# LED.net
KiCad netlist of a schematic drawn in Altium Designer
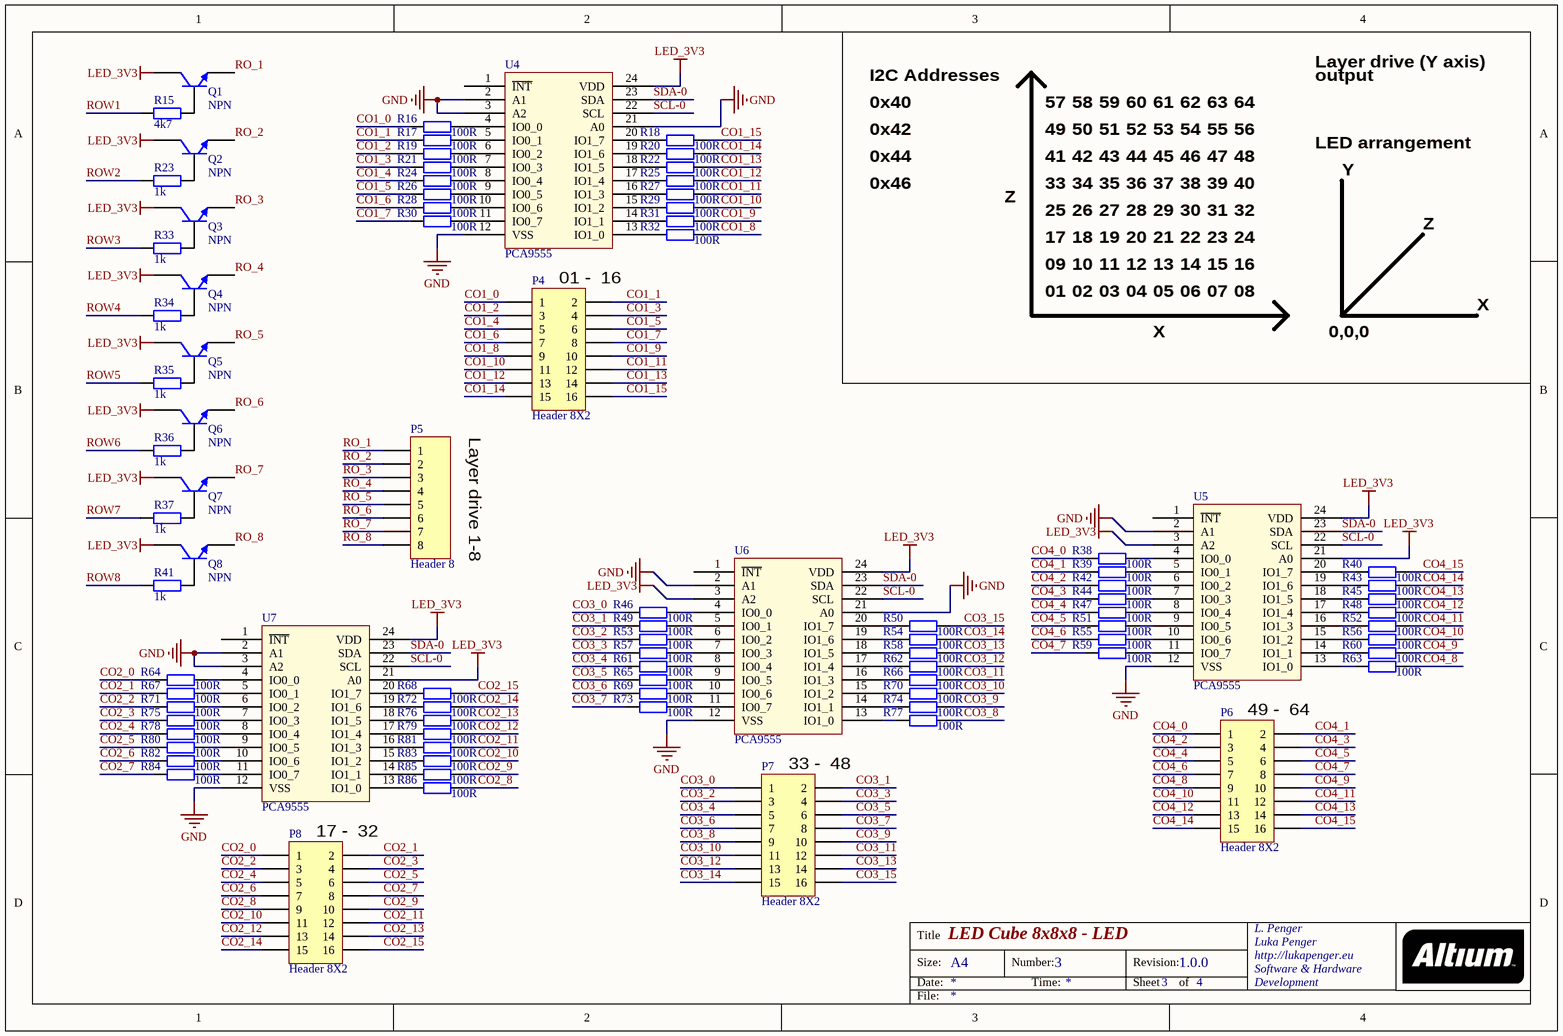
[diagram p0: LED.SchDoc]

(export (version "E")
  (design (tool "Eeschema 10.0.6"))
  (components
    (comp (ref "P4")
      (value "Header 8X2")
      (footprint "HDR2X8")
      (description "Header, 8-Pin, Dual row")
      (fields (field (name "PUBLISHER") "Altium Limited"))
      (libsource (lib "Miscellaneous Connectors") (part "Header 8X2"))
    )
    (comp (ref "P5")
      (value "Header 8")
      (footprint "HDR1X8")
      (description "Header, 8-Pin")
      (fields (field (name "PUBLISHER") "Altium Limited"))
      (libsource (lib "Miscellaneous Connectors") (part "Header 8"))
    )
    (comp (ref "P6")
      (value "Header 8X2")
      (footprint "HDR2X8")
      (description "Header, 8-Pin, Dual row")
      (fields (field (name "PUBLISHER") "Altium Limited"))
      (libsource (lib "Miscellaneous Connectors") (part "Header 8X2"))
    )
    (comp (ref "P7")
      (value "Header 8X2")
      (footprint "HDR2X8")
      (description "Header, 8-Pin, Dual row")
      (fields (field (name "PUBLISHER") "Altium Limited"))
      (libsource (lib "Miscellaneous Connectors") (part "Header 8X2"))
    )
    (comp (ref "P8")
      (value "Header 8X2")
      (footprint "HDR2X8")
      (description "Header, 8-Pin, Dual row")
      (fields (field (name "PUBLISHER") "Altium Limited"))
      (libsource (lib "Miscellaneous Connectors") (part "Header 8X2"))
    )
    (comp (ref "Q1")
      (value "NPN")
      (footprint "SOT23_L")
      (description "NPN Bipolar Transistor")
      (fields (field (name "PUBLISHER") "Altium Limited"))
      (libsource (lib "Miscellaneous Devices") (part "NPN"))
    )
    (comp (ref "Q2")
      (value "NPN")
      (footprint "SOT23_L")
      (description "NPN Bipolar Transistor")
      (fields (field (name "PUBLISHER") "Altium Limited"))
      (libsource (lib "Miscellaneous Devices") (part "NPN"))
    )
    (comp (ref "Q3")
      (value "NPN")
      (footprint "SOT23_L")
      (description "NPN Bipolar Transistor")
      (fields (field (name "PUBLISHER") "Altium Limited"))
      (libsource (lib "Miscellaneous Devices") (part "NPN"))
    )
    (comp (ref "Q4")
      (value "NPN")
      (footprint "SOT23_L")
      (description "NPN Bipolar Transistor")
      (fields (field (name "PUBLISHER") "Altium Limited"))
      (libsource (lib "Miscellaneous Devices") (part "NPN"))
    )
    (comp (ref "Q5")
      (value "NPN")
      (footprint "SOT23_L")
      (description "NPN Bipolar Transistor")
      (fields (field (name "PUBLISHER") "Altium Limited"))
      (libsource (lib "Miscellaneous Devices") (part "NPN"))
    )
    (comp (ref "Q6")
      (value "NPN")
      (footprint "SOT23_L")
      (description "NPN Bipolar Transistor")
      (fields (field (name "PUBLISHER") "Altium Limited"))
      (libsource (lib "Miscellaneous Devices") (part "NPN"))
    )
    (comp (ref "Q7")
      (value "NPN")
      (footprint "SOT23_L")
      (description "NPN Bipolar Transistor")
      (fields (field (name "PUBLISHER") "Altium Limited"))
      (libsource (lib "Miscellaneous Devices") (part "NPN"))
    )
    (comp (ref "Q8")
      (value "NPN")
      (footprint "SOT23_L")
      (description "NPN Bipolar Transistor")
      (fields (field (name "PUBLISHER") "Altium Limited"))
      (libsource (lib "Miscellaneous Devices") (part "NPN"))
    )
    (comp (ref "R15")
      (value "4k7")
      (footprint "6-0805_N")
      (description "Resistor")
      (fields (field (name "PUBLISHER") "Altium Limited"))
      (libsource (lib "") (part "Res2_1"))
    )
    (comp (ref "R16")
      (value "100R")
      (footprint "6-0805_L")
      (description "Resistor")
      (fields (field (name "PUBLISHER") "Altium Limited"))
      (libsource (lib "Miscellaneous Devices") (part "Res2"))
    )
    (comp (ref "R17")
      (value "100R")
      (footprint "6-0805_L")
      (description "Resistor")
      (fields (field (name "PUBLISHER") "Altium Limited"))
      (libsource (lib "Miscellaneous Devices") (part "Res2"))
    )
    (comp (ref "R18")
      (value "100R")
      (footprint "6-0805_L")
      (description "Resistor")
      (fields (field (name "PUBLISHER") "Altium Limited"))
      (libsource (lib "Miscellaneous Devices") (part "Res2"))
    )
    (comp (ref "R19")
      (value "100R")
      (footprint "6-0805_L")
      (description "Resistor")
      (fields (field (name "PUBLISHER") "Altium Limited"))
      (libsource (lib "Miscellaneous Devices") (part "Res2"))
    )
    (comp (ref "R20")
      (value "100R")
      (footprint "6-0805_L")
      (description "Resistor")
      (fields (field (name "PUBLISHER") "Altium Limited"))
      (libsource (lib "Miscellaneous Devices") (part "Res2"))
    )
    (comp (ref "R21")
      (value "100R")
      (footprint "6-0805_L")
      (description "Resistor")
      (fields (field (name "PUBLISHER") "Altium Limited"))
      (libsource (lib "Miscellaneous Devices") (part "Res2"))
    )
    (comp (ref "R22")
      (value "100R")
      (footprint "6-0805_L")
      (description "Resistor")
      (fields (field (name "PUBLISHER") "Altium Limited"))
      (libsource (lib "Miscellaneous Devices") (part "Res2"))
    )
    (comp (ref "R23")
      (value "1k")
      (footprint "6-0805_N")
      (description "Resistor")
      (fields (field (name "PUBLISHER") "Altium Limited"))
      (libsource (lib "") (part "Res2_1"))
    )
    (comp (ref "R24")
      (value "100R")
      (footprint "6-0805_L")
      (description "Resistor")
      (fields (field (name "PUBLISHER") "Altium Limited"))
      (libsource (lib "Miscellaneous Devices") (part "Res2"))
    )
    (comp (ref "R25")
      (value "100R")
      (footprint "6-0805_L")
      (description "Resistor")
      (fields (field (name "PUBLISHER") "Altium Limited"))
      (libsource (lib "Miscellaneous Devices") (part "Res2"))
    )
    (comp (ref "R26")
      (value "100R")
      (footprint "6-0805_L")
      (description "Resistor")
      (fields (field (name "PUBLISHER") "Altium Limited"))
      (libsource (lib "Miscellaneous Devices") (part "Res2"))
    )
    (comp (ref "R27")
      (value "100R")
      (footprint "6-0805_L")
      (description "Resistor")
      (fields (field (name "PUBLISHER") "Altium Limited"))
      (libsource (lib "Miscellaneous Devices") (part "Res2"))
    )
    (comp (ref "R28")
      (value "100R")
      (footprint "6-0805_L")
      (description "Resistor")
      (fields (field (name "PUBLISHER") "Altium Limited"))
      (libsource (lib "Miscellaneous Devices") (part "Res2"))
    )
    (comp (ref "R29")
      (value "100R")
      (footprint "6-0805_L")
      (description "Resistor")
      (fields (field (name "PUBLISHER") "Altium Limited"))
      (libsource (lib "Miscellaneous Devices") (part "Res2"))
    )
    (comp (ref "R30")
      (value "100R")
      (footprint "6-0805_L")
      (description "Resistor")
      (fields (field (name "PUBLISHER") "Altium Limited"))
      (libsource (lib "Miscellaneous Devices") (part "Res2"))
    )
    (comp (ref "R31")
      (value "100R")
      (footprint "6-0805_L")
      (description "Resistor")
      (fields (field (name "PUBLISHER") "Altium Limited"))
      (libsource (lib "Miscellaneous Devices") (part "Res2"))
    )
    (comp (ref "R32")
      (value "100R")
      (footprint "6-0805_L")
      (description "Resistor")
      (fields (field (name "PUBLISHER") "Altium Limited"))
      (libsource (lib "Miscellaneous Devices") (part "Res2"))
    )
    (comp (ref "R33")
      (value "1k")
      (footprint "6-0805_N")
      (description "Resistor")
      (fields (field (name "PUBLISHER") "Altium Limited"))
      (libsource (lib "") (part "Res2_1"))
    )
    (comp (ref "R34")
      (value "1k")
      (footprint "6-0805_N")
      (description "Resistor")
      (fields (field (name "PUBLISHER") "Altium Limited"))
      (libsource (lib "") (part "Res2_1"))
    )
    (comp (ref "R35")
      (value "1k")
      (footprint "6-0805_N")
      (description "Resistor")
      (fields (field (name "PUBLISHER") "Altium Limited"))
      (libsource (lib "") (part "Res2_1"))
    )
    (comp (ref "R36")
      (value "1k")
      (footprint "6-0805_N")
      (description "Resistor")
      (fields (field (name "PUBLISHER") "Altium Limited"))
      (libsource (lib "") (part "Res2_1"))
    )
    (comp (ref "R37")
      (value "1k")
      (footprint "6-0805_N")
      (description "Resistor")
      (fields (field (name "PUBLISHER") "Altium Limited"))
      (libsource (lib "") (part "Res2_1"))
    )
    (comp (ref "R38")
      (value "100R")
      (footprint "6-0805_L")
      (description "Resistor")
      (fields (field (name "PUBLISHER") "Altium Limited"))
      (libsource (lib "Miscellaneous Devices") (part "Res2"))
    )
    (comp (ref "R39")
      (value "100R")
      (footprint "6-0805_L")
      (description "Resistor")
      (fields (field (name "PUBLISHER") "Altium Limited"))
      (libsource (lib "Miscellaneous Devices") (part "Res2"))
    )
    (comp (ref "R40")
      (value "100R")
      (footprint "6-0805_L")
      (description "Resistor")
      (fields (field (name "PUBLISHER") "Altium Limited"))
      (libsource (lib "Miscellaneous Devices") (part "Res2"))
    )
    (comp (ref "R41")
      (value "1k")
      (footprint "6-0805_N")
      (description "Resistor")
      (fields (field (name "PUBLISHER") "Altium Limited"))
      (libsource (lib "") (part "Res2_1"))
    )
    (comp (ref "R42")
      (value "100R")
      (footprint "6-0805_L")
      (description "Resistor")
      (fields (field (name "PUBLISHER") "Altium Limited"))
      (libsource (lib "Miscellaneous Devices") (part "Res2"))
    )
    (comp (ref "R43")
      (value "100R")
      (footprint "6-0805_L")
      (description "Resistor")
      (fields (field (name "PUBLISHER") "Altium Limited"))
      (libsource (lib "Miscellaneous Devices") (part "Res2"))
    )
    (comp (ref "R44")
      (value "100R")
      (footprint "6-0805_L")
      (description "Resistor")
      (fields (field (name "PUBLISHER") "Altium Limited"))
      (libsource (lib "Miscellaneous Devices") (part "Res2"))
    )
    (comp (ref "R45")
      (value "100R")
      (footprint "6-0805_L")
      (description "Resistor")
      (fields (field (name "PUBLISHER") "Altium Limited"))
      (libsource (lib "Miscellaneous Devices") (part "Res2"))
    )
    (comp (ref "R46")
      (value "100R")
      (footprint "6-0805_L")
      (description "Resistor")
      (fields (field (name "PUBLISHER") "Altium Limited"))
      (libsource (lib "Miscellaneous Devices") (part "Res2"))
    )
    (comp (ref "R47")
      (value "100R")
      (footprint "6-0805_L")
      (description "Resistor")
      (fields (field (name "PUBLISHER") "Altium Limited"))
      (libsource (lib "Miscellaneous Devices") (part "Res2"))
    )
    (comp (ref "R48")
      (value "100R")
      (footprint "6-0805_L")
      (description "Resistor")
      (fields (field (name "PUBLISHER") "Altium Limited"))
      (libsource (lib "Miscellaneous Devices") (part "Res2"))
    )
    (comp (ref "R49")
      (value "100R")
      (footprint "6-0805_L")
      (description "Resistor")
      (fields (field (name "PUBLISHER") "Altium Limited"))
      (libsource (lib "Miscellaneous Devices") (part "Res2"))
    )
    (comp (ref "R50")
      (value "100R")
      (footprint "6-0805_L")
      (description "Resistor")
      (fields (field (name "PUBLISHER") "Altium Limited"))
      (libsource (lib "Miscellaneous Devices") (part "Res2"))
    )
    (comp (ref "R51")
      (value "100R")
      (footprint "6-0805_L")
      (description "Resistor")
      (fields (field (name "PUBLISHER") "Altium Limited"))
      (libsource (lib "Miscellaneous Devices") (part "Res2"))
    )
    (comp (ref "R52")
      (value "100R")
      (footprint "6-0805_L")
      (description "Resistor")
      (fields (field (name "PUBLISHER") "Altium Limited"))
      (libsource (lib "Miscellaneous Devices") (part "Res2"))
    )
    (comp (ref "R53")
      (value "100R")
      (footprint "6-0805_L")
      (description "Resistor")
      (fields (field (name "PUBLISHER") "Altium Limited"))
      (libsource (lib "Miscellaneous Devices") (part "Res2"))
    )
    (comp (ref "R54")
      (value "100R")
      (footprint "6-0805_L")
      (description "Resistor")
      (fields (field (name "PUBLISHER") "Altium Limited"))
      (libsource (lib "Miscellaneous Devices") (part "Res2"))
    )
    (comp (ref "R55")
      (value "100R")
      (footprint "6-0805_L")
      (description "Resistor")
      (fields (field (name "PUBLISHER") "Altium Limited"))
      (libsource (lib "Miscellaneous Devices") (part "Res2"))
    )
    (comp (ref "R56")
      (value "100R")
      (footprint "6-0805_L")
      (description "Resistor")
      (fields (field (name "PUBLISHER") "Altium Limited"))
      (libsource (lib "Miscellaneous Devices") (part "Res2"))
    )
    (comp (ref "R57")
      (value "100R")
      (footprint "6-0805_L")
      (description "Resistor")
      (fields (field (name "PUBLISHER") "Altium Limited"))
      (libsource (lib "Miscellaneous Devices") (part "Res2"))
    )
    (comp (ref "R58")
      (value "100R")
      (footprint "6-0805_L")
      (description "Resistor")
      (fields (field (name "PUBLISHER") "Altium Limited"))
      (libsource (lib "Miscellaneous Devices") (part "Res2"))
    )
    (comp (ref "R59")
      (value "100R")
      (footprint "6-0805_L")
      (description "Resistor")
      (fields (field (name "PUBLISHER") "Altium Limited"))
      (libsource (lib "Miscellaneous Devices") (part "Res2"))
    )
    (comp (ref "R60")
      (value "100R")
      (footprint "6-0805_L")
      (description "Resistor")
      (fields (field (name "PUBLISHER") "Altium Limited"))
      (libsource (lib "Miscellaneous Devices") (part "Res2"))
    )
    (comp (ref "R61")
      (value "100R")
      (footprint "6-0805_L")
      (description "Resistor")
      (fields (field (name "PUBLISHER") "Altium Limited"))
      (libsource (lib "Miscellaneous Devices") (part "Res2"))
    )
    (comp (ref "R62")
      (value "100R")
      (footprint "6-0805_L")
      (description "Resistor")
      (fields (field (name "PUBLISHER") "Altium Limited"))
      (libsource (lib "Miscellaneous Devices") (part "Res2"))
    )
    (comp (ref "R63")
      (value "100R")
      (footprint "6-0805_L")
      (description "Resistor")
      (fields (field (name "PUBLISHER") "Altium Limited"))
      (libsource (lib "Miscellaneous Devices") (part "Res2"))
    )
    (comp (ref "R64")
      (value "100R")
      (footprint "6-0805_L")
      (description "Resistor")
      (fields (field (name "PUBLISHER") "Altium Limited"))
      (libsource (lib "Miscellaneous Devices") (part "Res2"))
    )
    (comp (ref "R65")
      (value "100R")
      (footprint "6-0805_L")
      (description "Resistor")
      (fields (field (name "PUBLISHER") "Altium Limited"))
      (libsource (lib "Miscellaneous Devices") (part "Res2"))
    )
    (comp (ref "R66")
      (value "100R")
      (footprint "6-0805_L")
      (description "Resistor")
      (fields (field (name "PUBLISHER") "Altium Limited"))
      (libsource (lib "Miscellaneous Devices") (part "Res2"))
    )
    (comp (ref "R67")
      (value "100R")
      (footprint "6-0805_L")
      (description "Resistor")
      (fields (field (name "PUBLISHER") "Altium Limited"))
      (libsource (lib "Miscellaneous Devices") (part "Res2"))
    )
    (comp (ref "R68")
      (value "100R")
      (footprint "6-0805_L")
      (description "Resistor")
      (fields (field (name "PUBLISHER") "Altium Limited"))
      (libsource (lib "Miscellaneous Devices") (part "Res2"))
    )
    (comp (ref "R69")
      (value "100R")
      (footprint "6-0805_L")
      (description "Resistor")
      (fields (field (name "PUBLISHER") "Altium Limited"))
      (libsource (lib "Miscellaneous Devices") (part "Res2"))
    )
    (comp (ref "R70")
      (value "100R")
      (footprint "6-0805_L")
      (description "Resistor")
      (fields (field (name "PUBLISHER") "Altium Limited"))
      (libsource (lib "Miscellaneous Devices") (part "Res2"))
    )
    (comp (ref "R71")
      (value "100R")
      (footprint "6-0805_L")
      (description "Resistor")
      (fields (field (name "PUBLISHER") "Altium Limited"))
      (libsource (lib "Miscellaneous Devices") (part "Res2"))
    )
    (comp (ref "R72")
      (value "100R")
      (footprint "6-0805_L")
      (description "Resistor")
      (fields (field (name "PUBLISHER") "Altium Limited"))
      (libsource (lib "Miscellaneous Devices") (part "Res2"))
    )
    (comp (ref "R73")
      (value "100R")
      (footprint "6-0805_L")
      (description "Resistor")
      (fields (field (name "PUBLISHER") "Altium Limited"))
      (libsource (lib "Miscellaneous Devices") (part "Res2"))
    )
    (comp (ref "R74")
      (value "100R")
      (footprint "6-0805_L")
      (description "Resistor")
      (fields (field (name "PUBLISHER") "Altium Limited"))
      (libsource (lib "Miscellaneous Devices") (part "Res2"))
    )
    (comp (ref "R75")
      (value "100R")
      (footprint "6-0805_L")
      (description "Resistor")
      (fields (field (name "PUBLISHER") "Altium Limited"))
      (libsource (lib "Miscellaneous Devices") (part "Res2"))
    )
    (comp (ref "R76")
      (value "100R")
      (footprint "6-0805_L")
      (description "Resistor")
      (fields (field (name "PUBLISHER") "Altium Limited"))
      (libsource (lib "Miscellaneous Devices") (part "Res2"))
    )
    (comp (ref "R77")
      (value "100R")
      (footprint "6-0805_L")
      (description "Resistor")
      (fields (field (name "PUBLISHER") "Altium Limited"))
      (libsource (lib "Miscellaneous Devices") (part "Res2"))
    )
    (comp (ref "R78")
      (value "100R")
      (footprint "6-0805_L")
      (description "Resistor")
      (fields (field (name "PUBLISHER") "Altium Limited"))
      (libsource (lib "Miscellaneous Devices") (part "Res2"))
    )
    (comp (ref "R79")
      (value "100R")
      (footprint "6-0805_L")
      (description "Resistor")
      (fields (field (name "PUBLISHER") "Altium Limited"))
      (libsource (lib "Miscellaneous Devices") (part "Res2"))
    )
    (comp (ref "R80")
      (value "100R")
      (footprint "6-0805_L")
      (description "Resistor")
      (fields (field (name "PUBLISHER") "Altium Limited"))
      (libsource (lib "Miscellaneous Devices") (part "Res2"))
    )
    (comp (ref "R81")
      (value "100R")
      (footprint "6-0805_L")
      (description "Resistor")
      (fields (field (name "PUBLISHER") "Altium Limited"))
      (libsource (lib "Miscellaneous Devices") (part "Res2"))
    )
    (comp (ref "R82")
      (value "100R")
      (footprint "6-0805_L")
      (description "Resistor")
      (fields (field (name "PUBLISHER") "Altium Limited"))
      (libsource (lib "Miscellaneous Devices") (part "Res2"))
    )
    (comp (ref "R83")
      (value "100R")
      (footprint "6-0805_L")
      (description "Resistor")
      (fields (field (name "PUBLISHER") "Altium Limited"))
      (libsource (lib "Miscellaneous Devices") (part "Res2"))
    )
    (comp (ref "R84")
      (value "100R")
      (footprint "6-0805_L")
      (description "Resistor")
      (fields (field (name "PUBLISHER") "Altium Limited"))
      (libsource (lib "Miscellaneous Devices") (part "Res2"))
    )
    (comp (ref "R85")
      (value "100R")
      (footprint "6-0805_L")
      (description "Resistor")
      (fields (field (name "PUBLISHER") "Altium Limited"))
      (libsource (lib "Miscellaneous Devices") (part "Res2"))
    )
    (comp (ref "R86")
      (value "100R")
      (footprint "6-0805_L")
      (description "Resistor")
      (fields (field (name "PUBLISHER") "Altium Limited"))
      (libsource (lib "Miscellaneous Devices") (part "Res2"))
    )
    (comp (ref "U4")
      (value "PCA9555")
      (footprint "SSOP24_N")
      (description "I2C I/O Ports")
      (libsource (lib "LP_Lib") (part "PCA9555"))
    )
    (comp (ref "U5")
      (value "PCA9555")
      (footprint "SSOP24_N")
      (description "I2C I/O Ports")
      (libsource (lib "LP_Lib") (part "PCA9555"))
    )
    (comp (ref "U6")
      (value "PCA9555")
      (footprint "SSOP24_N")
      (description "I2C I/O Ports")
      (libsource (lib "LP_Lib") (part "PCA9555"))
    )
    (comp (ref "U7")
      (value "PCA9555")
      (footprint "SSOP24_N")
      (description "I2C I/O Ports")
      (libsource (lib "LP_Lib") (part "PCA9555"))
    )
  )
  (nets
    (net (code "1") (name "/CO1_0") (class "Default")
      (node (ref "P4") (pin "1") (pinfunction "1_1") (pintype "passive"))
      (node (ref "R16") (pin "1") (pinfunction "1_1") (pintype "passive"))
    )
    (net (code "2") (name "/CO1_1") (class "Default")
      (node (ref "P4") (pin "2") (pinfunction "2_2") (pintype "passive"))
      (node (ref "R17") (pin "1") (pinfunction "1_1") (pintype "passive"))
    )
    (net (code "3") (name "/CO1_2") (class "Default")
      (node (ref "P4") (pin "3") (pinfunction "3_3") (pintype "passive"))
      (node (ref "R19") (pin "1") (pinfunction "1_1") (pintype "passive"))
    )
    (net (code "4") (name "/CO1_3") (class "Default")
      (node (ref "P4") (pin "4") (pinfunction "4_4") (pintype "passive"))
      (node (ref "R21") (pin "1") (pinfunction "1_1") (pintype "passive"))
    )
    (net (code "5") (name "/CO1_4") (class "Default")
      (node (ref "P4") (pin "5") (pinfunction "5_5") (pintype "passive"))
      (node (ref "R24") (pin "1") (pinfunction "1_1") (pintype "passive"))
    )
    (net (code "6") (name "/CO1_5") (class "Default")
      (node (ref "P4") (pin "6") (pinfunction "6_6") (pintype "passive"))
      (node (ref "R26") (pin "1") (pinfunction "1_1") (pintype "passive"))
    )
    (net (code "7") (name "/CO1_6") (class "Default")
      (node (ref "P4") (pin "7") (pinfunction "7_7") (pintype "passive"))
      (node (ref "R28") (pin "1") (pinfunction "1_1") (pintype "passive"))
    )
    (net (code "8") (name "/CO1_7") (class "Default")
      (node (ref "P4") (pin "8") (pinfunction "8_8") (pintype "passive"))
      (node (ref "R30") (pin "1") (pinfunction "1_1") (pintype "passive"))
    )
    (net (code "9") (name "/CO1_8") (class "Default")
      (node (ref "P4") (pin "9") (pinfunction "9_9") (pintype "passive"))
      (node (ref "R32") (pin "2") (pinfunction "2_2") (pintype "passive"))
    )
    (net (code "10") (name "/CO1_9") (class "Default")
      (node (ref "P4") (pin "10") (pinfunction "10_10") (pintype "passive"))
      (node (ref "R31") (pin "2") (pinfunction "2_2") (pintype "passive"))
    )
    (net (code "11") (name "/CO1_10") (class "Default")
      (node (ref "P4") (pin "11") (pinfunction "11_11") (pintype "passive"))
      (node (ref "R29") (pin "2") (pinfunction "2_2") (pintype "passive"))
    )
    (net (code "12") (name "/CO1_11") (class "Default")
      (node (ref "P4") (pin "12") (pinfunction "12_12") (pintype "passive"))
      (node (ref "R27") (pin "2") (pinfunction "2_2") (pintype "passive"))
    )
    (net (code "13") (name "/CO1_12") (class "Default")
      (node (ref "P4") (pin "13") (pinfunction "13_13") (pintype "passive"))
      (node (ref "R25") (pin "2") (pinfunction "2_2") (pintype "passive"))
    )
    (net (code "14") (name "/CO1_13") (class "Default")
      (node (ref "P4") (pin "14") (pinfunction "14_14") (pintype "passive"))
      (node (ref "R22") (pin "2") (pinfunction "2_2") (pintype "passive"))
    )
    (net (code "15") (name "/CO1_14") (class "Default")
      (node (ref "P4") (pin "15") (pinfunction "15_15") (pintype "passive"))
      (node (ref "R20") (pin "2") (pinfunction "2_2") (pintype "passive"))
    )
    (net (code "16") (name "/CO1_15") (class "Default")
      (node (ref "P4") (pin "16") (pinfunction "16_16") (pintype "passive"))
      (node (ref "R18") (pin "2") (pinfunction "2_2") (pintype "passive"))
    )
    (net (code "17") (name "/CO2_0") (class "Default")
      (node (ref "P8") (pin "1") (pinfunction "1_1") (pintype "passive"))
      (node (ref "R64") (pin "1") (pinfunction "1_1") (pintype "passive"))
    )
    (net (code "18") (name "/CO2_1") (class "Default")
      (node (ref "P8") (pin "2") (pinfunction "2_2") (pintype "passive"))
      (node (ref "R67") (pin "1") (pinfunction "1_1") (pintype "passive"))
    )
    (net (code "19") (name "/CO2_2") (class "Default")
      (node (ref "P8") (pin "3") (pinfunction "3_3") (pintype "passive"))
      (node (ref "R71") (pin "1") (pinfunction "1_1") (pintype "passive"))
    )
    (net (code "20") (name "/CO2_3") (class "Default")
      (node (ref "P8") (pin "4") (pinfunction "4_4") (pintype "passive"))
      (node (ref "R75") (pin "1") (pinfunction "1_1") (pintype "passive"))
    )
    (net (code "21") (name "/CO2_4") (class "Default")
      (node (ref "P8") (pin "5") (pinfunction "5_5") (pintype "passive"))
      (node (ref "R78") (pin "1") (pinfunction "1_1") (pintype "passive"))
    )
    (net (code "22") (name "/CO2_5") (class "Default")
      (node (ref "P8") (pin "6") (pinfunction "6_6") (pintype "passive"))
      (node (ref "R80") (pin "1") (pinfunction "1_1") (pintype "passive"))
    )
    (net (code "23") (name "/CO2_6") (class "Default")
      (node (ref "P8") (pin "7") (pinfunction "7_7") (pintype "passive"))
      (node (ref "R82") (pin "1") (pinfunction "1_1") (pintype "passive"))
    )
    (net (code "24") (name "/CO2_7") (class "Default")
      (node (ref "P8") (pin "8") (pinfunction "8_8") (pintype "passive"))
      (node (ref "R84") (pin "1") (pinfunction "1_1") (pintype "passive"))
    )
    (net (code "25") (name "/CO2_8") (class "Default")
      (node (ref "P8") (pin "9") (pinfunction "9_9") (pintype "passive"))
      (node (ref "R86") (pin "2") (pinfunction "2_2") (pintype "passive"))
    )
    (net (code "26") (name "/CO2_9") (class "Default")
      (node (ref "P8") (pin "10") (pinfunction "10_10") (pintype "passive"))
      (node (ref "R85") (pin "2") (pinfunction "2_2") (pintype "passive"))
    )
    (net (code "27") (name "/CO2_10") (class "Default")
      (node (ref "P8") (pin "11") (pinfunction "11_11") (pintype "passive"))
      (node (ref "R83") (pin "2") (pinfunction "2_2") (pintype "passive"))
    )
    (net (code "28") (name "/CO2_11") (class "Default")
      (node (ref "P8") (pin "12") (pinfunction "12_12") (pintype "passive"))
      (node (ref "R81") (pin "2") (pinfunction "2_2") (pintype "passive"))
    )
    (net (code "29") (name "/CO2_12") (class "Default")
      (node (ref "P8") (pin "13") (pinfunction "13_13") (pintype "passive"))
      (node (ref "R79") (pin "2") (pinfunction "2_2") (pintype "passive"))
    )
    (net (code "30") (name "/CO2_13") (class "Default")
      (node (ref "P8") (pin "14") (pinfunction "14_14") (pintype "passive"))
      (node (ref "R76") (pin "2") (pinfunction "2_2") (pintype "passive"))
    )
    (net (code "31") (name "/CO2_14") (class "Default")
      (node (ref "P8") (pin "15") (pinfunction "15_15") (pintype "passive"))
      (node (ref "R72") (pin "2") (pinfunction "2_2") (pintype "passive"))
    )
    (net (code "32") (name "/CO2_15") (class "Default")
      (node (ref "P8") (pin "16") (pinfunction "16_16") (pintype "passive"))
      (node (ref "R68") (pin "2") (pinfunction "2_2") (pintype "passive"))
    )
    (net (code "33") (name "/CO3_0") (class "Default")
      (node (ref "P7") (pin "1") (pinfunction "1_1") (pintype "passive"))
      (node (ref "R46") (pin "1") (pinfunction "1_1") (pintype "passive"))
    )
    (net (code "34") (name "/CO3_1") (class "Default")
      (node (ref "P7") (pin "2") (pinfunction "2_2") (pintype "passive"))
      (node (ref "R49") (pin "1") (pinfunction "1_1") (pintype "passive"))
    )
    (net (code "35") (name "/CO3_2") (class "Default")
      (node (ref "P7") (pin "3") (pinfunction "3_3") (pintype "passive"))
      (node (ref "R53") (pin "1") (pinfunction "1_1") (pintype "passive"))
    )
    (net (code "36") (name "/CO3_3") (class "Default")
      (node (ref "P7") (pin "4") (pinfunction "4_4") (pintype "passive"))
      (node (ref "R57") (pin "1") (pinfunction "1_1") (pintype "passive"))
    )
    (net (code "37") (name "/CO3_4") (class "Default")
      (node (ref "P7") (pin "5") (pinfunction "5_5") (pintype "passive"))
      (node (ref "R61") (pin "1") (pinfunction "1_1") (pintype "passive"))
    )
    (net (code "38") (name "/CO3_5") (class "Default")
      (node (ref "P7") (pin "6") (pinfunction "6_6") (pintype "passive"))
      (node (ref "R65") (pin "1") (pinfunction "1_1") (pintype "passive"))
    )
    (net (code "39") (name "/CO3_6") (class "Default")
      (node (ref "P7") (pin "7") (pinfunction "7_7") (pintype "passive"))
      (node (ref "R69") (pin "1") (pinfunction "1_1") (pintype "passive"))
    )
    (net (code "40") (name "/CO3_7") (class "Default")
      (node (ref "P7") (pin "8") (pinfunction "8_8") (pintype "passive"))
      (node (ref "R73") (pin "1") (pinfunction "1_1") (pintype "passive"))
    )
    (net (code "41") (name "/CO3_8") (class "Default")
      (node (ref "P7") (pin "9") (pinfunction "9_9") (pintype "passive"))
      (node (ref "R77") (pin "2") (pinfunction "2_2") (pintype "passive"))
    )
    (net (code "42") (name "/CO3_9") (class "Default")
      (node (ref "P7") (pin "10") (pinfunction "10_10") (pintype "passive"))
      (node (ref "R74") (pin "2") (pinfunction "2_2") (pintype "passive"))
    )
    (net (code "43") (name "/CO3_10") (class "Default")
      (node (ref "P7") (pin "11") (pinfunction "11_11") (pintype "passive"))
      (node (ref "R70") (pin "2") (pinfunction "2_2") (pintype "passive"))
    )
    (net (code "44") (name "/CO3_11") (class "Default")
      (node (ref "P7") (pin "12") (pinfunction "12_12") (pintype "passive"))
      (node (ref "R66") (pin "2") (pinfunction "2_2") (pintype "passive"))
    )
    (net (code "45") (name "/CO3_12") (class "Default")
      (node (ref "P7") (pin "13") (pinfunction "13_13") (pintype "passive"))
      (node (ref "R62") (pin "2") (pinfunction "2_2") (pintype "passive"))
    )
    (net (code "46") (name "/CO3_13") (class "Default")
      (node (ref "P7") (pin "14") (pinfunction "14_14") (pintype "passive"))
      (node (ref "R58") (pin "2") (pinfunction "2_2") (pintype "passive"))
    )
    (net (code "47") (name "/CO3_14") (class "Default")
      (node (ref "P7") (pin "15") (pinfunction "15_15") (pintype "passive"))
      (node (ref "R54") (pin "2") (pinfunction "2_2") (pintype "passive"))
    )
    (net (code "48") (name "/CO3_15") (class "Default")
      (node (ref "P7") (pin "16") (pinfunction "16_16") (pintype "passive"))
      (node (ref "R50") (pin "2") (pinfunction "2_2") (pintype "passive"))
    )
    (net (code "49") (name "/CO4_0") (class "Default")
      (node (ref "P6") (pin "1") (pinfunction "1_1") (pintype "passive"))
      (node (ref "R38") (pin "1") (pinfunction "1_1") (pintype "passive"))
    )
    (net (code "50") (name "/CO4_1") (class "Default")
      (node (ref "P6") (pin "2") (pinfunction "2_2") (pintype "passive"))
      (node (ref "R39") (pin "1") (pinfunction "1_1") (pintype "passive"))
    )
    (net (code "51") (name "/CO4_2") (class "Default")
      (node (ref "P6") (pin "3") (pinfunction "3_3") (pintype "passive"))
      (node (ref "R42") (pin "1") (pinfunction "1_1") (pintype "passive"))
    )
    (net (code "52") (name "/CO4_3") (class "Default")
      (node (ref "P6") (pin "4") (pinfunction "4_4") (pintype "passive"))
      (node (ref "R44") (pin "1") (pinfunction "1_1") (pintype "passive"))
    )
    (net (code "53") (name "/CO4_4") (class "Default")
      (node (ref "P6") (pin "5") (pinfunction "5_5") (pintype "passive"))
      (node (ref "R47") (pin "1") (pinfunction "1_1") (pintype "passive"))
    )
    (net (code "54") (name "/CO4_5") (class "Default")
      (node (ref "P6") (pin "6") (pinfunction "6_6") (pintype "passive"))
      (node (ref "R51") (pin "1") (pinfunction "1_1") (pintype "passive"))
    )
    (net (code "55") (name "/CO4_6") (class "Default")
      (node (ref "P6") (pin "7") (pinfunction "7_7") (pintype "passive"))
      (node (ref "R55") (pin "1") (pinfunction "1_1") (pintype "passive"))
    )
    (net (code "56") (name "/CO4_7") (class "Default")
      (node (ref "P6") (pin "8") (pinfunction "8_8") (pintype "passive"))
      (node (ref "R59") (pin "1") (pinfunction "1_1") (pintype "passive"))
    )
    (net (code "57") (name "/CO4_8") (class "Default")
      (node (ref "P6") (pin "9") (pinfunction "9_9") (pintype "passive"))
      (node (ref "R63") (pin "2") (pinfunction "2_2") (pintype "passive"))
    )
    (net (code "58") (name "/CO4_9") (class "Default")
      (node (ref "P6") (pin "10") (pinfunction "10_10") (pintype "passive"))
      (node (ref "R60") (pin "2") (pinfunction "2_2") (pintype "passive"))
    )
    (net (code "59") (name "/CO4_10") (class "Default")
      (node (ref "P6") (pin "11") (pinfunction "11_11") (pintype "passive"))
      (node (ref "R56") (pin "2") (pinfunction "2_2") (pintype "passive"))
    )
    (net (code "60") (name "/CO4_11") (class "Default")
      (node (ref "P6") (pin "12") (pinfunction "12_12") (pintype "passive"))
      (node (ref "R52") (pin "2") (pinfunction "2_2") (pintype "passive"))
    )
    (net (code "61") (name "/CO4_12") (class "Default")
      (node (ref "P6") (pin "13") (pinfunction "13_13") (pintype "passive"))
      (node (ref "R48") (pin "2") (pinfunction "2_2") (pintype "passive"))
    )
    (net (code "62") (name "/CO4_13") (class "Default")
      (node (ref "P6") (pin "14") (pinfunction "14_14") (pintype "passive"))
      (node (ref "R45") (pin "2") (pinfunction "2_2") (pintype "passive"))
    )
    (net (code "63") (name "/CO4_14") (class "Default")
      (node (ref "P6") (pin "15") (pinfunction "15_15") (pintype "passive"))
      (node (ref "R43") (pin "2") (pinfunction "2_2") (pintype "passive"))
    )
    (net (code "64") (name "/CO4_15") (class "Default")
      (node (ref "P6") (pin "16") (pinfunction "16_16") (pintype "passive"))
      (node (ref "R40") (pin "2") (pinfunction "2_2") (pintype "passive"))
    )
    (net (code "65") (name "/ROW1") (class "Default")
      (node (ref "R15") (pin "2") (pinfunction "2_2") (pintype "passive"))
    )
    (net (code "66") (name "/ROW2") (class "Default")
      (node (ref "R23") (pin "2") (pinfunction "2_2") (pintype "passive"))
    )
    (net (code "67") (name "/ROW3") (class "Default")
      (node (ref "R33") (pin "2") (pinfunction "2_2") (pintype "passive"))
    )
    (net (code "68") (name "/ROW4") (class "Default")
      (node (ref "R34") (pin "2") (pinfunction "2_2") (pintype "passive"))
    )
    (net (code "69") (name "/ROW5") (class "Default")
      (node (ref "R35") (pin "2") (pinfunction "2_2") (pintype "passive"))
    )
    (net (code "70") (name "/ROW6") (class "Default")
      (node (ref "R36") (pin "2") (pinfunction "2_2") (pintype "passive"))
    )
    (net (code "71") (name "/ROW7") (class "Default")
      (node (ref "R37") (pin "2") (pinfunction "2_2") (pintype "passive"))
    )
    (net (code "72") (name "/ROW8") (class "Default")
      (node (ref "R41") (pin "2") (pinfunction "2_2") (pintype "passive"))
    )
    (net (code "73") (name "/RO_1") (class "Default")
      (node (ref "P5") (pin "1") (pinfunction "1_1") (pintype "passive"))
      (node (ref "Q1") (pin "3") (pinfunction "E_3") (pintype "passive"))
    )
    (net (code "74") (name "/RO_2") (class "Default")
      (node (ref "P5") (pin "2") (pinfunction "2_2") (pintype "passive"))
      (node (ref "Q2") (pin "3") (pinfunction "E_3") (pintype "passive"))
    )
    (net (code "75") (name "/RO_3") (class "Default")
      (node (ref "P5") (pin "3") (pinfunction "3_3") (pintype "passive"))
      (node (ref "Q3") (pin "3") (pinfunction "E_3") (pintype "passive"))
    )
    (net (code "76") (name "/RO_4") (class "Default")
      (node (ref "P5") (pin "4") (pinfunction "4_4") (pintype "passive"))
      (node (ref "Q4") (pin "3") (pinfunction "E_3") (pintype "passive"))
    )
    (net (code "77") (name "/RO_5") (class "Default")
      (node (ref "P5") (pin "5") (pinfunction "5_5") (pintype "passive"))
      (node (ref "Q5") (pin "3") (pinfunction "E_3") (pintype "passive"))
    )
    (net (code "78") (name "/RO_6") (class "Default")
      (node (ref "P5") (pin "6") (pinfunction "6_6") (pintype "passive"))
      (node (ref "Q6") (pin "3") (pinfunction "E_3") (pintype "passive"))
    )
    (net (code "79") (name "/RO_7") (class "Default")
      (node (ref "P5") (pin "7") (pinfunction "7_7") (pintype "passive"))
      (node (ref "Q7") (pin "3") (pinfunction "E_3") (pintype "passive"))
    )
    (net (code "80") (name "/RO_8") (class "Default")
      (node (ref "P5") (pin "8") (pinfunction "8_8") (pintype "passive"))
      (node (ref "Q8") (pin "3") (pinfunction "E_3") (pintype "passive"))
    )
    (net (code "81") (name "/SCL-0") (class "Default")
      (node (ref "U4") (pin "22") (pinfunction "SCL_22") (pintype "passive"))
      (node (ref "U5") (pin "22") (pinfunction "SCL_22") (pintype "passive"))
      (node (ref "U6") (pin "22") (pinfunction "SCL_22") (pintype "passive"))
      (node (ref "U7") (pin "22") (pinfunction "SCL_22") (pintype "passive"))
    )
    (net (code "82") (name "/SDA-0") (class "Default")
      (node (ref "U4") (pin "23") (pinfunction "SDA_23") (pintype "passive"))
      (node (ref "U5") (pin "23") (pinfunction "SDA_23") (pintype "passive"))
      (node (ref "U6") (pin "23") (pinfunction "SDA_23") (pintype "passive"))
      (node (ref "U7") (pin "23") (pinfunction "SDA_23") (pintype "passive"))
    )
    (net (code "83") (name "GND") (class "Default")
      (node (ref "U4") (pin "12") (pinfunction "VSS_12") (pintype "passive"))
      (node (ref "U4") (pin "2") (pinfunction "A1_2") (pintype "passive"))
      (node (ref "U4") (pin "21") (pinfunction "A0_21") (pintype "passive"))
      (node (ref "U4") (pin "3") (pinfunction "A2_3") (pintype "passive"))
      (node (ref "U5") (pin "12") (pinfunction "VSS_12") (pintype "passive"))
      (node (ref "U5") (pin "2") (pinfunction "A1_2") (pintype "passive"))
      (node (ref "U6") (pin "12") (pinfunction "VSS_12") (pintype "passive"))
      (node (ref "U6") (pin "2") (pinfunction "A1_2") (pintype "passive"))
      (node (ref "U6") (pin "21") (pinfunction "A0_21") (pintype "passive"))
      (node (ref "U7") (pin "12") (pinfunction "VSS_12") (pintype "passive"))
      (node (ref "U7") (pin "2") (pinfunction "A1_2") (pintype "passive"))
      (node (ref "U7") (pin "3") (pinfunction "A2_3") (pintype "passive"))
    )
    (net (code "84") (name "LED_3V3") (class "Default")
      (node (ref "Q1") (pin "1") (pinfunction "C_1") (pintype "passive"))
      (node (ref "Q2") (pin "1") (pinfunction "C_1") (pintype "passive"))
      (node (ref "Q3") (pin "1") (pinfunction "C_1") (pintype "passive"))
      (node (ref "Q4") (pin "1") (pinfunction "C_1") (pintype "passive"))
      (node (ref "Q5") (pin "1") (pinfunction "C_1") (pintype "passive"))
      (node (ref "Q6") (pin "1") (pinfunction "C_1") (pintype "passive"))
      (node (ref "Q7") (pin "1") (pinfunction "C_1") (pintype "passive"))
      (node (ref "Q8") (pin "1") (pinfunction "C_1") (pintype "passive"))
      (node (ref "U4") (pin "24") (pinfunction "VDD_24") (pintype "passive"))
      (node (ref "U5") (pin "21") (pinfunction "A0_21") (pintype "passive"))
      (node (ref "U5") (pin "24") (pinfunction "VDD_24") (pintype "passive"))
      (node (ref "U5") (pin "3") (pinfunction "A2_3") (pintype "passive"))
      (node (ref "U6") (pin "24") (pinfunction "VDD_24") (pintype "passive"))
      (node (ref "U6") (pin "3") (pinfunction "A2_3") (pintype "passive"))
      (node (ref "U7") (pin "21") (pinfunction "A0_21") (pintype "passive"))
      (node (ref "U7") (pin "24") (pinfunction "VDD_24") (pintype "passive"))
    )
    (net (code "85") (name "Net-(Q1-B)") (class "Default")
      (node (ref "Q1") (pin "2") (pinfunction "B_2") (pintype "passive"))
      (node (ref "R15") (pin "1") (pinfunction "1_1") (pintype "passive"))
    )
    (net (code "86") (name "Net-(Q2-B)") (class "Default")
      (node (ref "Q2") (pin "2") (pinfunction "B_2") (pintype "passive"))
      (node (ref "R23") (pin "1") (pinfunction "1_1") (pintype "passive"))
    )
    (net (code "87") (name "Net-(Q3-B)") (class "Default")
      (node (ref "Q3") (pin "2") (pinfunction "B_2") (pintype "passive"))
      (node (ref "R33") (pin "1") (pinfunction "1_1") (pintype "passive"))
    )
    (net (code "88") (name "Net-(Q4-B)") (class "Default")
      (node (ref "Q4") (pin "2") (pinfunction "B_2") (pintype "passive"))
      (node (ref "R34") (pin "1") (pinfunction "1_1") (pintype "passive"))
    )
    (net (code "89") (name "Net-(Q5-B)") (class "Default")
      (node (ref "Q5") (pin "2") (pinfunction "B_2") (pintype "passive"))
      (node (ref "R35") (pin "1") (pinfunction "1_1") (pintype "passive"))
    )
    (net (code "90") (name "Net-(Q6-B)") (class "Default")
      (node (ref "Q6") (pin "2") (pinfunction "B_2") (pintype "passive"))
      (node (ref "R36") (pin "1") (pinfunction "1_1") (pintype "passive"))
    )
    (net (code "91") (name "Net-(Q7-B)") (class "Default")
      (node (ref "Q7") (pin "2") (pinfunction "B_2") (pintype "passive"))
      (node (ref "R37") (pin "1") (pinfunction "1_1") (pintype "passive"))
    )
    (net (code "92") (name "Net-(Q8-B)") (class "Default")
      (node (ref "Q8") (pin "2") (pinfunction "B_2") (pintype "passive"))
      (node (ref "R41") (pin "1") (pinfunction "1_1") (pintype "passive"))
    )
    (net (code "93") (name "Net-(U4-IO0_0)") (class "Default")
      (node (ref "R16") (pin "2") (pinfunction "2_2") (pintype "passive"))
      (node (ref "U4") (pin "4") (pinfunction "IO0_0_4") (pintype "passive"))
    )
    (net (code "94") (name "Net-(U4-IO0_1)") (class "Default")
      (node (ref "R17") (pin "2") (pinfunction "2_2") (pintype "passive"))
      (node (ref "U4") (pin "5") (pinfunction "IO0_1_5") (pintype "passive"))
    )
    (net (code "95") (name "Net-(U4-IO0_2)") (class "Default")
      (node (ref "R19") (pin "2") (pinfunction "2_2") (pintype "passive"))
      (node (ref "U4") (pin "6") (pinfunction "IO0_2_6") (pintype "passive"))
    )
    (net (code "96") (name "Net-(U4-IO0_3)") (class "Default")
      (node (ref "R21") (pin "2") (pinfunction "2_2") (pintype "passive"))
      (node (ref "U4") (pin "7") (pinfunction "IO0_3_7") (pintype "passive"))
    )
    (net (code "97") (name "Net-(U4-IO0_4)") (class "Default")
      (node (ref "R24") (pin "2") (pinfunction "2_2") (pintype "passive"))
      (node (ref "U4") (pin "8") (pinfunction "IO0_4_8") (pintype "passive"))
    )
    (net (code "98") (name "Net-(U4-IO0_5)") (class "Default")
      (node (ref "R26") (pin "2") (pinfunction "2_2") (pintype "passive"))
      (node (ref "U4") (pin "9") (pinfunction "IO0_5_9") (pintype "passive"))
    )
    (net (code "99") (name "Net-(U4-IO0_6)") (class "Default")
      (node (ref "R28") (pin "2") (pinfunction "2_2") (pintype "passive"))
      (node (ref "U4") (pin "10") (pinfunction "IO0_6_10") (pintype "passive"))
    )
    (net (code "100") (name "Net-(U4-IO0_7)") (class "Default")
      (node (ref "R30") (pin "2") (pinfunction "2_2") (pintype "passive"))
      (node (ref "U4") (pin "11") (pinfunction "IO0_7_11") (pintype "passive"))
    )
    (net (code "101") (name "Net-(U4-IO1_0)") (class "Default")
      (node (ref "R32") (pin "1") (pinfunction "1_1") (pintype "passive"))
      (node (ref "U4") (pin "13") (pinfunction "IO1_0_13") (pintype "passive"))
    )
    (net (code "102") (name "Net-(U4-IO1_1)") (class "Default")
      (node (ref "R31") (pin "1") (pinfunction "1_1") (pintype "passive"))
      (node (ref "U4") (pin "14") (pinfunction "IO1_1_14") (pintype "passive"))
    )
    (net (code "103") (name "Net-(U4-IO1_2)") (class "Default")
      (node (ref "R29") (pin "1") (pinfunction "1_1") (pintype "passive"))
      (node (ref "U4") (pin "15") (pinfunction "IO1_2_15") (pintype "passive"))
    )
    (net (code "104") (name "Net-(U4-IO1_3)") (class "Default")
      (node (ref "R27") (pin "1") (pinfunction "1_1") (pintype "passive"))
      (node (ref "U4") (pin "16") (pinfunction "IO1_3_16") (pintype "passive"))
    )
    (net (code "105") (name "Net-(U4-IO1_4)") (class "Default")
      (node (ref "R25") (pin "1") (pinfunction "1_1") (pintype "passive"))
      (node (ref "U4") (pin "17") (pinfunction "IO1_4_17") (pintype "passive"))
    )
    (net (code "106") (name "Net-(U4-IO1_5)") (class "Default")
      (node (ref "R22") (pin "1") (pinfunction "1_1") (pintype "passive"))
      (node (ref "U4") (pin "18") (pinfunction "IO1_5_18") (pintype "passive"))
    )
    (net (code "107") (name "Net-(U4-IO1_6)") (class "Default")
      (node (ref "R20") (pin "1") (pinfunction "1_1") (pintype "passive"))
      (node (ref "U4") (pin "19") (pinfunction "IO1_6_19") (pintype "passive"))
    )
    (net (code "108") (name "Net-(U4-IO1_7)") (class "Default")
      (node (ref "R18") (pin "1") (pinfunction "1_1") (pintype "passive"))
      (node (ref "U4") (pin "20") (pinfunction "IO1_7_20") (pintype "passive"))
    )
    (net (code "109") (name "Net-(U5-IO0_0)") (class "Default")
      (node (ref "R38") (pin "2") (pinfunction "2_2") (pintype "passive"))
      (node (ref "U5") (pin "4") (pinfunction "IO0_0_4") (pintype "passive"))
    )
    (net (code "110") (name "Net-(U5-IO0_1)") (class "Default")
      (node (ref "R39") (pin "2") (pinfunction "2_2") (pintype "passive"))
      (node (ref "U5") (pin "5") (pinfunction "IO0_1_5") (pintype "passive"))
    )
    (net (code "111") (name "Net-(U5-IO0_2)") (class "Default")
      (node (ref "R42") (pin "2") (pinfunction "2_2") (pintype "passive"))
      (node (ref "U5") (pin "6") (pinfunction "IO0_2_6") (pintype "passive"))
    )
    (net (code "112") (name "Net-(U5-IO0_3)") (class "Default")
      (node (ref "R44") (pin "2") (pinfunction "2_2") (pintype "passive"))
      (node (ref "U5") (pin "7") (pinfunction "IO0_3_7") (pintype "passive"))
    )
    (net (code "113") (name "Net-(U5-IO0_4)") (class "Default")
      (node (ref "R47") (pin "2") (pinfunction "2_2") (pintype "passive"))
      (node (ref "U5") (pin "8") (pinfunction "IO0_4_8") (pintype "passive"))
    )
    (net (code "114") (name "Net-(U5-IO0_5)") (class "Default")
      (node (ref "R51") (pin "2") (pinfunction "2_2") (pintype "passive"))
      (node (ref "U5") (pin "9") (pinfunction "IO0_5_9") (pintype "passive"))
    )
    (net (code "115") (name "Net-(U5-IO0_6)") (class "Default")
      (node (ref "R55") (pin "2") (pinfunction "2_2") (pintype "passive"))
      (node (ref "U5") (pin "10") (pinfunction "IO0_6_10") (pintype "passive"))
    )
    (net (code "116") (name "Net-(U5-IO0_7)") (class "Default")
      (node (ref "R59") (pin "2") (pinfunction "2_2") (pintype "passive"))
      (node (ref "U5") (pin "11") (pinfunction "IO0_7_11") (pintype "passive"))
    )
    (net (code "117") (name "Net-(U5-IO1_0)") (class "Default")
      (node (ref "R63") (pin "1") (pinfunction "1_1") (pintype "passive"))
      (node (ref "U5") (pin "13") (pinfunction "IO1_0_13") (pintype "passive"))
    )
    (net (code "118") (name "Net-(U5-IO1_1)") (class "Default")
      (node (ref "R60") (pin "1") (pinfunction "1_1") (pintype "passive"))
      (node (ref "U5") (pin "14") (pinfunction "IO1_1_14") (pintype "passive"))
    )
    (net (code "119") (name "Net-(U5-IO1_2)") (class "Default")
      (node (ref "R56") (pin "1") (pinfunction "1_1") (pintype "passive"))
      (node (ref "U5") (pin "15") (pinfunction "IO1_2_15") (pintype "passive"))
    )
    (net (code "120") (name "Net-(U5-IO1_3)") (class "Default")
      (node (ref "R52") (pin "1") (pinfunction "1_1") (pintype "passive"))
      (node (ref "U5") (pin "16") (pinfunction "IO1_3_16") (pintype "passive"))
    )
    (net (code "121") (name "Net-(U5-IO1_4)") (class "Default")
      (node (ref "R48") (pin "1") (pinfunction "1_1") (pintype "passive"))
      (node (ref "U5") (pin "17") (pinfunction "IO1_4_17") (pintype "passive"))
    )
    (net (code "122") (name "Net-(U5-IO1_5)") (class "Default")
      (node (ref "R45") (pin "1") (pinfunction "1_1") (pintype "passive"))
      (node (ref "U5") (pin "18") (pinfunction "IO1_5_18") (pintype "passive"))
    )
    (net (code "123") (name "Net-(U5-IO1_6)") (class "Default")
      (node (ref "R43") (pin "1") (pinfunction "1_1") (pintype "passive"))
      (node (ref "U5") (pin "19") (pinfunction "IO1_6_19") (pintype "passive"))
    )
    (net (code "124") (name "Net-(U5-IO1_7)") (class "Default")
      (node (ref "R40") (pin "1") (pinfunction "1_1") (pintype "passive"))
      (node (ref "U5") (pin "20") (pinfunction "IO1_7_20") (pintype "passive"))
    )
    (net (code "125") (name "Net-(U6-IO0_0)") (class "Default")
      (node (ref "R46") (pin "2") (pinfunction "2_2") (pintype "passive"))
      (node (ref "U6") (pin "4") (pinfunction "IO0_0_4") (pintype "passive"))
    )
    (net (code "126") (name "Net-(U6-IO0_1)") (class "Default")
      (node (ref "R49") (pin "2") (pinfunction "2_2") (pintype "passive"))
      (node (ref "U6") (pin "5") (pinfunction "IO0_1_5") (pintype "passive"))
    )
    (net (code "127") (name "Net-(U6-IO0_2)") (class "Default")
      (node (ref "R53") (pin "2") (pinfunction "2_2") (pintype "passive"))
      (node (ref "U6") (pin "6") (pinfunction "IO0_2_6") (pintype "passive"))
    )
    (net (code "128") (name "Net-(U6-IO0_3)") (class "Default")
      (node (ref "R57") (pin "2") (pinfunction "2_2") (pintype "passive"))
      (node (ref "U6") (pin "7") (pinfunction "IO0_3_7") (pintype "passive"))
    )
    (net (code "129") (name "Net-(U6-IO0_4)") (class "Default")
      (node (ref "R61") (pin "2") (pinfunction "2_2") (pintype "passive"))
      (node (ref "U6") (pin "8") (pinfunction "IO0_4_8") (pintype "passive"))
    )
    (net (code "130") (name "Net-(U6-IO0_5)") (class "Default")
      (node (ref "R65") (pin "2") (pinfunction "2_2") (pintype "passive"))
      (node (ref "U6") (pin "9") (pinfunction "IO0_5_9") (pintype "passive"))
    )
    (net (code "131") (name "Net-(U6-IO0_6)") (class "Default")
      (node (ref "R69") (pin "2") (pinfunction "2_2") (pintype "passive"))
      (node (ref "U6") (pin "10") (pinfunction "IO0_6_10") (pintype "passive"))
    )
    (net (code "132") (name "Net-(U6-IO0_7)") (class "Default")
      (node (ref "R73") (pin "2") (pinfunction "2_2") (pintype "passive"))
      (node (ref "U6") (pin "11") (pinfunction "IO0_7_11") (pintype "passive"))
    )
    (net (code "133") (name "Net-(U6-IO1_0)") (class "Default")
      (node (ref "R77") (pin "1") (pinfunction "1_1") (pintype "passive"))
      (node (ref "U6") (pin "13") (pinfunction "IO1_0_13") (pintype "passive"))
    )
    (net (code "134") (name "Net-(U6-IO1_1)") (class "Default")
      (node (ref "R74") (pin "1") (pinfunction "1_1") (pintype "passive"))
      (node (ref "U6") (pin "14") (pinfunction "IO1_1_14") (pintype "passive"))
    )
    (net (code "135") (name "Net-(U6-IO1_2)") (class "Default")
      (node (ref "R70") (pin "1") (pinfunction "1_1") (pintype "passive"))
      (node (ref "U6") (pin "15") (pinfunction "IO1_2_15") (pintype "passive"))
    )
    (net (code "136") (name "Net-(U6-IO1_3)") (class "Default")
      (node (ref "R66") (pin "1") (pinfunction "1_1") (pintype "passive"))
      (node (ref "U6") (pin "16") (pinfunction "IO1_3_16") (pintype "passive"))
    )
    (net (code "137") (name "Net-(U6-IO1_4)") (class "Default")
      (node (ref "R62") (pin "1") (pinfunction "1_1") (pintype "passive"))
      (node (ref "U6") (pin "17") (pinfunction "IO1_4_17") (pintype "passive"))
    )
    (net (code "138") (name "Net-(U6-IO1_5)") (class "Default")
      (node (ref "R58") (pin "1") (pinfunction "1_1") (pintype "passive"))
      (node (ref "U6") (pin "18") (pinfunction "IO1_5_18") (pintype "passive"))
    )
    (net (code "139") (name "Net-(U6-IO1_6)") (class "Default")
      (node (ref "R54") (pin "1") (pinfunction "1_1") (pintype "passive"))
      (node (ref "U6") (pin "19") (pinfunction "IO1_6_19") (pintype "passive"))
    )
    (net (code "140") (name "Net-(U6-IO1_7)") (class "Default")
      (node (ref "R50") (pin "1") (pinfunction "1_1") (pintype "passive"))
      (node (ref "U6") (pin "20") (pinfunction "IO1_7_20") (pintype "passive"))
    )
    (net (code "141") (name "Net-(U7-IO0_0)") (class "Default")
      (node (ref "R64") (pin "2") (pinfunction "2_2") (pintype "passive"))
      (node (ref "U7") (pin "4") (pinfunction "IO0_0_4") (pintype "passive"))
    )
    (net (code "142") (name "Net-(U7-IO0_1)") (class "Default")
      (node (ref "R67") (pin "2") (pinfunction "2_2") (pintype "passive"))
      (node (ref "U7") (pin "5") (pinfunction "IO0_1_5") (pintype "passive"))
    )
    (net (code "143") (name "Net-(U7-IO0_2)") (class "Default")
      (node (ref "R71") (pin "2") (pinfunction "2_2") (pintype "passive"))
      (node (ref "U7") (pin "6") (pinfunction "IO0_2_6") (pintype "passive"))
    )
    (net (code "144") (name "Net-(U7-IO0_3)") (class "Default")
      (node (ref "R75") (pin "2") (pinfunction "2_2") (pintype "passive"))
      (node (ref "U7") (pin "7") (pinfunction "IO0_3_7") (pintype "passive"))
    )
    (net (code "145") (name "Net-(U7-IO0_4)") (class "Default")
      (node (ref "R78") (pin "2") (pinfunction "2_2") (pintype "passive"))
      (node (ref "U7") (pin "8") (pinfunction "IO0_4_8") (pintype "passive"))
    )
    (net (code "146") (name "Net-(U7-IO0_5)") (class "Default")
      (node (ref "R80") (pin "2") (pinfunction "2_2") (pintype "passive"))
      (node (ref "U7") (pin "9") (pinfunction "IO0_5_9") (pintype "passive"))
    )
    (net (code "147") (name "Net-(U7-IO0_6)") (class "Default")
      (node (ref "R82") (pin "2") (pinfunction "2_2") (pintype "passive"))
      (node (ref "U7") (pin "10") (pinfunction "IO0_6_10") (pintype "passive"))
    )
    (net (code "148") (name "Net-(U7-IO0_7)") (class "Default")
      (node (ref "R84") (pin "2") (pinfunction "2_2") (pintype "passive"))
      (node (ref "U7") (pin "11") (pinfunction "IO0_7_11") (pintype "passive"))
    )
    (net (code "149") (name "Net-(U7-IO1_0)") (class "Default")
      (node (ref "R86") (pin "1") (pinfunction "1_1") (pintype "passive"))
      (node (ref "U7") (pin "13") (pinfunction "IO1_0_13") (pintype "passive"))
    )
    (net (code "150") (name "Net-(U7-IO1_1)") (class "Default")
      (node (ref "R85") (pin "1") (pinfunction "1_1") (pintype "passive"))
      (node (ref "U7") (pin "14") (pinfunction "IO1_1_14") (pintype "passive"))
    )
    (net (code "151") (name "Net-(U7-IO1_2)") (class "Default")
      (node (ref "R83") (pin "1") (pinfunction "1_1") (pintype "passive"))
      (node (ref "U7") (pin "15") (pinfunction "IO1_2_15") (pintype "passive"))
    )
    (net (code "152") (name "Net-(U7-IO1_3)") (class "Default")
      (node (ref "R81") (pin "1") (pinfunction "1_1") (pintype "passive"))
      (node (ref "U7") (pin "16") (pinfunction "IO1_3_16") (pintype "passive"))
    )
    (net (code "153") (name "Net-(U7-IO1_4)") (class "Default")
      (node (ref "R79") (pin "1") (pinfunction "1_1") (pintype "passive"))
      (node (ref "U7") (pin "17") (pinfunction "IO1_4_17") (pintype "passive"))
    )
    (net (code "154") (name "Net-(U7-IO1_5)") (class "Default")
      (node (ref "R76") (pin "1") (pinfunction "1_1") (pintype "passive"))
      (node (ref "U7") (pin "18") (pinfunction "IO1_5_18") (pintype "passive"))
    )
    (net (code "155") (name "Net-(U7-IO1_6)") (class "Default")
      (node (ref "R72") (pin "1") (pinfunction "1_1") (pintype "passive"))
      (node (ref "U7") (pin "19") (pinfunction "IO1_6_19") (pintype "passive"))
    )
    (net (code "156") (name "Net-(U7-IO1_7)") (class "Default")
      (node (ref "R68") (pin "1") (pinfunction "1_1") (pintype "passive"))
      (node (ref "U7") (pin "20") (pinfunction "IO1_7_20") (pintype "passive"))
    )
    (net (code "157") (name "unconnected-(U4-~{INT}-Pad1)") (class "Default")
      (node (ref "U4") (pin "1") (pinfunction "~{INT}_1") (pintype "passive"))
    )
    (net (code "158") (name "unconnected-(U5-~{INT}-Pad1)") (class "Default")
      (node (ref "U5") (pin "1") (pinfunction "~{INT}_1") (pintype "passive"))
    )
    (net (code "159") (name "unconnected-(U6-~{INT}-Pad1)") (class "Default")
      (node (ref "U6") (pin "1") (pinfunction "~{INT}_1") (pintype "passive"))
    )
    (net (code "160") (name "unconnected-(U7-~{INT}-Pad1)") (class "Default")
      (node (ref "U7") (pin "1") (pinfunction "~{INT}_1") (pintype "passive"))
    )
  )
)
